# EEPROM_M24C02_DFN8.net
KiCad netlist of a schematic drawn in Altium Designer
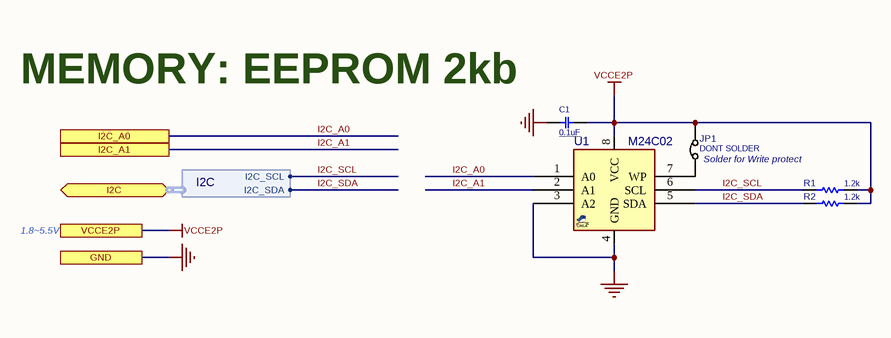
[diagram p0: EEPROM_M24C02_DFN8.SchDoc]

(export (version "E")
  (design (tool "Eeschema 10.0.6"))
  (components
    (comp (ref "C1")
      (value "0.1uF")
      (footprint "C0402")
      (description "CAP, MLCC")
      (fields (field (name "MANF_P#") "MANF_PART#") (field (name "MANF") "Murata"))
      (libsource (lib "passive_smd") (part "CAP_SMD_MLCC"))
    )
    (comp (ref "JP1")
      (value "DONT SOLDER")
      (footprint "JP_40X50")
      (description "JUMPER,  solder")
      (fields (field (name "MANF") "MANF") (field (name "MANF_P#") "MANF_P#"))
      (libsource (lib "test-tp_jumper") (part "JUMPER_SOLDER"))
    )
    (comp (ref "R1")
      (value "1.2k")
      (footprint "R0402")
      (description "RESISTOR, SMD")
      (libsource (lib "passive_smd") (part "RES_SMD"))
    )
    (comp (ref "R2")
      (value "1.2k")
      (footprint "R0402")
      (description "RESISTOR, SMD")
      (libsource (lib "passive_smd") (part "RES_SMD"))
    )
    (comp (ref "U1")
      (value "M24C02")
      (footprint "SON50_8T_2030")
      (description "EEPROM, I2C, 2Kb, 1MHz, DFN-8")
      (fields (field (name "MANF") "ST") (field (name "MANF_P#") "M24C02-DRMF3TG/K"))
      (libsource (lib "memory_eeprom_I2C") (part "EEPROM_I2C_M24C02_DFN8"))
    )
  )
  (nets
    (net (code "2") (name "/I2C_A0") (class "Default")
      (node (ref "U1") (pin "1") (pinfunction "A0_1") (pintype "passive"))
    )
    (net (code "3") (name "/I2C_A1") (class "Default")
      (node (ref "U1") (pin "2") (pinfunction "A1_2") (pintype "passive"))
    )
    (net (code "4") (name "/I2C_SCL") (class "Default")
      (node (ref "R1") (pin "2") (pinfunction "2_2") (pintype "passive"))
      (node (ref "U1") (pin "6") (pinfunction "SCL_6") (pintype "passive"))
    )
    (net (code "5") (name "/I2C_SDA") (class "Default")
      (node (ref "R2") (pin "2") (pinfunction "2_2") (pintype "passive"))
      (node (ref "U1") (pin "5") (pinfunction "SDA_5") (pintype "passive"))
    )
    (net (code "7") (name "GND") (class "Default")
      (node (ref "C1") (pin "1") (pinfunction "1_1") (pintype "passive"))
      (node (ref "U1") (pin "3") (pinfunction "A2_3") (pintype "passive"))
      (node (ref "U1") (pin "4") (pinfunction "GND_4") (pintype "passive"))
    )
    (net (code "8") (name "Net-(U1-WP)") (class "Default")
      (node (ref "JP1") (pin "1") (pinfunction "1_1") (pintype "passive"))
      (node (ref "U1") (pin "7") (pinfunction "WP_7") (pintype "passive"))
    )
    (net (code "9") (name "VCCE2P") (class "Default")
      (node (ref "C1") (pin "2") (pinfunction "2_2") (pintype "passive"))
      (node (ref "JP1") (pin "2") (pinfunction "2_2") (pintype "passive"))
      (node (ref "R1") (pin "1") (pinfunction "1_1") (pintype "passive"))
      (node (ref "R2") (pin "1") (pinfunction "1_1") (pintype "passive"))
      (node (ref "U1") (pin "8") (pinfunction "VCC_8") (pintype "passive"))
    )
  )
)
